# Power_Input.net
KiCad netlist of a schematic drawn in Altium Designer
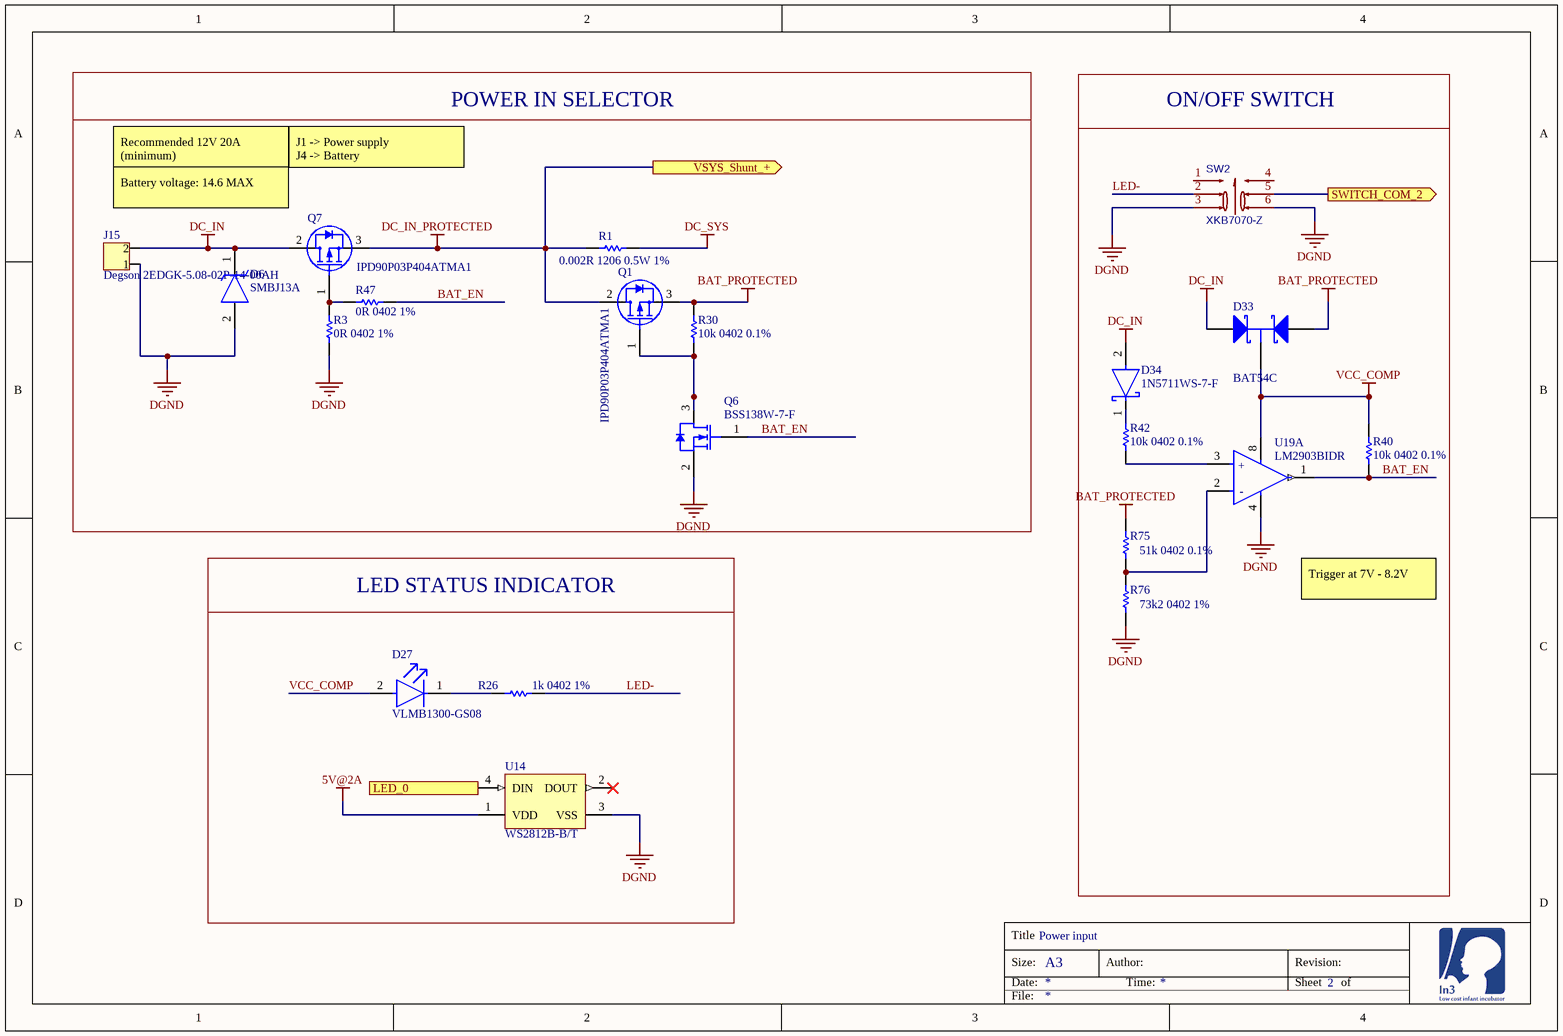
[diagram p0: Power_Input.SchDoc]

(export (version "E")
  (design (tool "Eeschema 10.0.6"))
  (components
    (comp (ref "D6")
      (value "SMBJ13A")
      (footprint "SamacSys:DIOM5436X244N")
      (description "TVS Diode (Uni-directional)")
      (libsource (lib "*") (part "SMBJ13A"))
    )
    (comp (ref "D27")
      (value "VLMB1300-GS08")
      (footprint "FP-6_541-5094_01-4-MFG")
      (description "LED BLUE 0603 SMD")
      (fields
        (field (name "MANUFACTURER") "Vishay Semiconductor Opto Division")
        (field (name "OCTOPART") "https://octopart.com/vlmb1300-gs08-vishay-22022408")
      )
      (libsource (lib "Altium Content Vault") (part "8706943c75ba83719d021d2fdc84c58"))
    )
    (comp (ref "D33")
      (value "BAT54C")
      (footprint "NXP-SOT23-3_V")
      (description "Schottky Barrier Diode, 30 V, 2 uA, -55 to 150 degC, 3-Pin SOT23, RoHS, Tape and Reel")
      (fields (field (name "MANUFACTURER") "NXP Semiconductors"))
      (libsource (lib "Altium Content Vault") (part "NXP-DSKY_A1A2K3-3"))
    )
    (comp (ref "D34")
      (value "1N5711WS-7-F")
      (footprint "FP-SOD323-MFG")
      (description "DIODE SCHOTTKY 70V 150MW SOD323")
      (fields
        (field (name "OCTOPART") "https://octopart.com/1n5711ws-7-f-diodes+inc.-323167")
        (field (name "MANUFACTURER") "Diodes Inc")
      )
      (libsource (lib "Altium Content Vault") (part "1d6ec82d83fb6aee721767c19dac4b9"))
    )
    (comp (ref "J15")
      (value "Degson 2EDGK-5.08-02P-14-00AH")
      (footprint "PCB-h4cyb3wxd4gf7j132tzl-1")
      (description "Terminal block, 5mm 2 Pos, through hole male.")
      (fields
        (field (name "MANUFACTURER PART NUMBER") "2EDGK-5.08-02P-14-00AH + 2EDGVC-5.08-02P")
        (field (name "LCSC PART") "C8445")
      )
      (libsource (lib "in3ator") (part "CMP-7a42b7ee166ba585-1"))
    )
    (comp (ref "Q1")
      (value "IPD90P03P404ATMA1")
      (footprint "DPAK IPD90P03P404ATMA1")
      (description "Single P-Channel 30 V 4.5 mOhm 100 nC OptiMOS Power Mosfet - TO-252-3-11")
      (libsource (lib "in3ator") (part "CMP-3103264-6"))
    )
    (comp (ref "Q6")
      (value "BSS138W-7-F")
      (footprint "DIOD-SOT323-3_V")
      (fields (field (name "MANUFACTURER") "DiodesIncorporated"))
      (libsource (lib "Altium Content Vault") (part "NEMOS-GSD-3"))
    )
    (comp (ref "Q7")
      (value "IPD90P03P404ATMA1")
      (footprint "DPAK IPD90P03P404ATMA1")
      (description "Single P-Channel 30 V 4.5 mOhm 100 nC OptiMOS Power Mosfet - TO-252-3-11")
      (libsource (lib "CommunityVault") (part "CMP-3103264-6"))
    )
    (comp (ref "R1")
      (value "0.002R 1206 0.5W 1%")
      (footprint "CAPC3216X180X55ML20T25")
      (fields (field (name "MANUFACTURER PART NUMBER") "WSLP12065L000FEA") (field (name "POWER") "1W"))
      (libsource (lib "in3ator") (part "CMP-0abdc173b10ad57a-1"))
    )
    (comp (ref "R3")
      (value "0R 0402 1%")
      (footprint "RESC1005X40X25ML05T10")
      (libsource (lib "Altium Content Vault") (part "RES"))
    )
    (comp (ref "R26")
      (value "1k 0402 1%")
      (footprint "RESC1005X40X25ML05T10")
      (libsource (lib "Altium Content Vault") (part "RES"))
    )
    (comp (ref "R30")
      (value "10k 0402 0.1%")
      (footprint "RESC1005X40X25ML05T10")
      (libsource (lib "Altium Content Vault") (part "RES"))
    )
    (comp (ref "R40")
      (value "10k 0402 0.1%")
      (footprint "RESC1005X40X25ML05T10")
      (libsource (lib "Altium Content Vault") (part "RES"))
    )
    (comp (ref "R42")
      (value "10k 0402 0.1%")
      (footprint "RESC1005X40X25ML05T10")
      (libsource (lib "Altium Content Vault") (part "RES"))
    )
    (comp (ref "R47")
      (value "0R 0402 1%")
      (footprint "RESC1005X40X25ML05T10")
      (libsource (lib "Altium Content Vault") (part "RES"))
    )
    (comp (ref "R75")
      (value "51k 0402 0.1%")
      (footprint "RESC1005X40X25ML05T10")
      (libsource (lib "Altium Content Vault") (part "RES"))
    )
    (comp (ref "R76")
      (value "73k2 0402 1%")
      (footprint "RESC1005X40X25ML05T10")
      (fields (field (name "MANUFACTURER") "Yageo / Phycomp"))
      (libsource (lib "Altium Content Vault") (part "RES"))
    )
    (comp (ref "SW2")
      (value "XKB7070-Z")
      (footprint "SW-TH_6P-L7.0-W7.0-P2.00")
      (fields (field (name "BOM_SUPPLIER PART") "C318863") (field (name "CONTRIBUTOR") "LCSC"))
      (libsource (lib "jlcpcb_components") (part "XKB7070-Z"))
    )
    (comp (ref "U14")
      (value "WS2812B-B/T")
      (footprint "ADA-RGB-1655_V")
      (fields (field (name "MANUFACTURER") "Adafruit-Industries-LLC"))
      (libsource (lib "Altium Content Vault") (part "ADA-RGB-1655-4"))
    )
    (comp (ref "U19")
      (value "LM2903BIDR")
      (footprint "FP-D0008A-MFG")
      (description "36V JI.3 DUAL COMPARATOR")
      (fields
        (field (name "OCTOPART") "https://octopart.com/lm2903bidr-texas+instruments-104977165")
        (field (name "MANUFACTURER") "Texas Instruments")
      )
      (libsource (lib "Altium Content Vault") (part "d0dfe35d032f86ae96c0c3919f86c94"))
    )
  )
  (nets
    (net (code "1") (name "/BAT_EN") (class "Default")
      (node (ref "Q6") (pin "1") (pinfunction "G_1") (pintype "passive"))
      (node (ref "R40") (pin "2") (pinfunction "2_2") (pintype "passive"))
      (node (ref "R47") (pin "2") (pinfunction "2_2") (pintype "passive"))
      (node (ref "U19") (pin "1") (pinfunction "1OUT_1") (pintype "output"))
    )
    (net (code "2") (name "/LED-") (class "Default")
      (node (ref "R26") (pin "1") (pinfunction "1_1") (pintype "passive"))
      (node (ref "SW2") (pin "2") (pinfunction "2_2") (pintype "passive"))
    )
    (net (code "3") (name "/LED_0") (class "Default")
      (node (ref "U14") (pin "4") (pinfunction "DIN_4") (pintype "input"))
    )
    (net (code "4") (name "/SWITCH_COM_2") (class "Default")
      (node (ref "SW2") (pin "5") (pinfunction "5_5") (pintype "passive"))
    )
    (net (code "5") (name "5V@2A") (class "Default")
      (node (ref "U14") (pin "1") (pinfunction "VDD_1") (pintype "power_in"))
    )
    (net (code "6") (name "BAT_PROTECTED") (class "Default")
      (node (ref "D33") (pin "2") (pinfunction "A_2") (pintype "passive"))
      (node (ref "Q1") (pin "3") (pinfunction "S_3") (pintype "passive"))
      (node (ref "R30") (pin "1") (pinfunction "1_1") (pintype "passive"))
      (node (ref "R75") (pin "2") (pinfunction "2_2") (pintype "passive"))
    )
    (net (code "7") (name "DC_IN") (class "Default")
      (node (ref "D33") (pin "1") (pinfunction "A_1") (pintype "passive"))
      (node (ref "D34") (pin "2") (pinfunction "A_2") (pintype "passive"))
      (node (ref "D6") (pin "1") (pinfunction "K_1") (pintype "passive"))
      (node (ref "J15") (pin "2") (pinfunction "2_2") (pintype "passive"))
      (node (ref "Q7") (pin "2") (pinfunction "D_2") (pintype "passive"))
    )
    (net (code "8") (name "DC_IN_PROTECTED") (class "Default")
      (node (ref "Q1") (pin "2") (pinfunction "D_2") (pintype "passive"))
      (node (ref "Q7") (pin "3") (pinfunction "S_3") (pintype "passive"))
      (node (ref "R1") (pin "2") (pinfunction "2_2") (pintype "passive"))
    )
    (net (code "9") (name "DC_SYS") (class "Default")
      (node (ref "R1") (pin "1") (pinfunction "1_1") (pintype "passive"))
    )
    (net (code "10") (name "DGND") (class "Default")
      (node (ref "D6") (pin "2") (pinfunction "A_2") (pintype "passive"))
      (node (ref "J15") (pin "1") (pinfunction "1_1") (pintype "passive"))
      (node (ref "Q6") (pin "2") (pinfunction "S_2") (pintype "passive"))
      (node (ref "R3") (pin "2") (pinfunction "2_2") (pintype "passive"))
      (node (ref "R76") (pin "1") (pinfunction "1_1") (pintype "passive"))
      (node (ref "SW2") (pin "3") (pinfunction "3_3") (pintype "passive"))
      (node (ref "SW2") (pin "6") (pinfunction "6_6") (pintype "passive"))
      (node (ref "U14") (pin "3") (pinfunction "VSS_3") (pintype "power_in"))
      (node (ref "U19") (pin "4") (pinfunction "GND_4") (pintype "power_in"))
    )
    (net (code "11") (name "Net-(D27-C)") (class "Default")
      (node (ref "D27") (pin "1") (pinfunction "C_1") (pintype "passive"))
      (node (ref "R26") (pin "2") (pinfunction "2_2") (pintype "passive"))
    )
    (net (code "12") (name "Net-(D34-C)") (class "Default")
      (node (ref "D34") (pin "1") (pinfunction "C_1") (pintype "passive"))
      (node (ref "R42") (pin "2") (pinfunction "2_2") (pintype "passive"))
    )
    (net (code "13") (name "Net-(Q1-G)") (class "Default")
      (node (ref "Q1") (pin "1") (pinfunction "G_1") (pintype "passive"))
      (node (ref "Q6") (pin "3") (pinfunction "D_3") (pintype "passive"))
      (node (ref "R30") (pin "2") (pinfunction "2_2") (pintype "passive"))
    )
    (net (code "14") (name "Net-(Q7-G)") (class "Default")
      (node (ref "Q7") (pin "1") (pinfunction "G_1") (pintype "passive"))
      (node (ref "R3") (pin "1") (pinfunction "1_1") (pintype "passive"))
      (node (ref "R47") (pin "1") (pinfunction "1_1") (pintype "passive"))
    )
    (net (code "15") (name "Net-(U19A-1IN+)") (class "Default")
      (node (ref "R42") (pin "1") (pinfunction "1_1") (pintype "passive"))
      (node (ref "U19") (pin "3") (pinfunction "1IN+_3") (pintype "tri_state"))
    )
    (net (code "16") (name "Net-(U19A-1IN-)") (class "Default")
      (node (ref "R75") (pin "1") (pinfunction "1_1") (pintype "passive"))
      (node (ref "R76") (pin "2") (pinfunction "2_2") (pintype "passive"))
      (node (ref "U19") (pin "2") (pinfunction "1IN-_2") (pintype "tri_state"))
    )
    (net (code "17") (name "VCC_COMP") (class "Default")
      (node (ref "D27") (pin "2") (pinfunction "A_2") (pintype "passive"))
      (node (ref "D33") (pin "3") (pinfunction "K_3") (pintype "passive"))
      (node (ref "R40") (pin "1") (pinfunction "1_1") (pintype "passive"))
      (node (ref "U19") (pin "8") (pinfunction "VCC_8") (pintype "power_in"))
    )
    (net (code "18") (name "unconnected-(SW2-Pad1)") (class "Default")
      (node (ref "SW2") (pin "1") (pinfunction "1_1") (pintype "passive"))
    )
    (net (code "19") (name "unconnected-(SW2-Pad4)") (class "Default")
      (node (ref "SW2") (pin "4") (pinfunction "4_4") (pintype "passive"))
    )
    (net (code "20") (name "unconnected-(U14-DOUT-Pad2)") (class "Default")
      (node (ref "U14") (pin "2") (pinfunction "DOUT_2") (pintype "output+no_connect"))
    )
  )
)
